# PIC18F57Q84_Curiosity_Nano_Target_MCU.net
KiCad netlist of a schematic drawn in Altium Designer
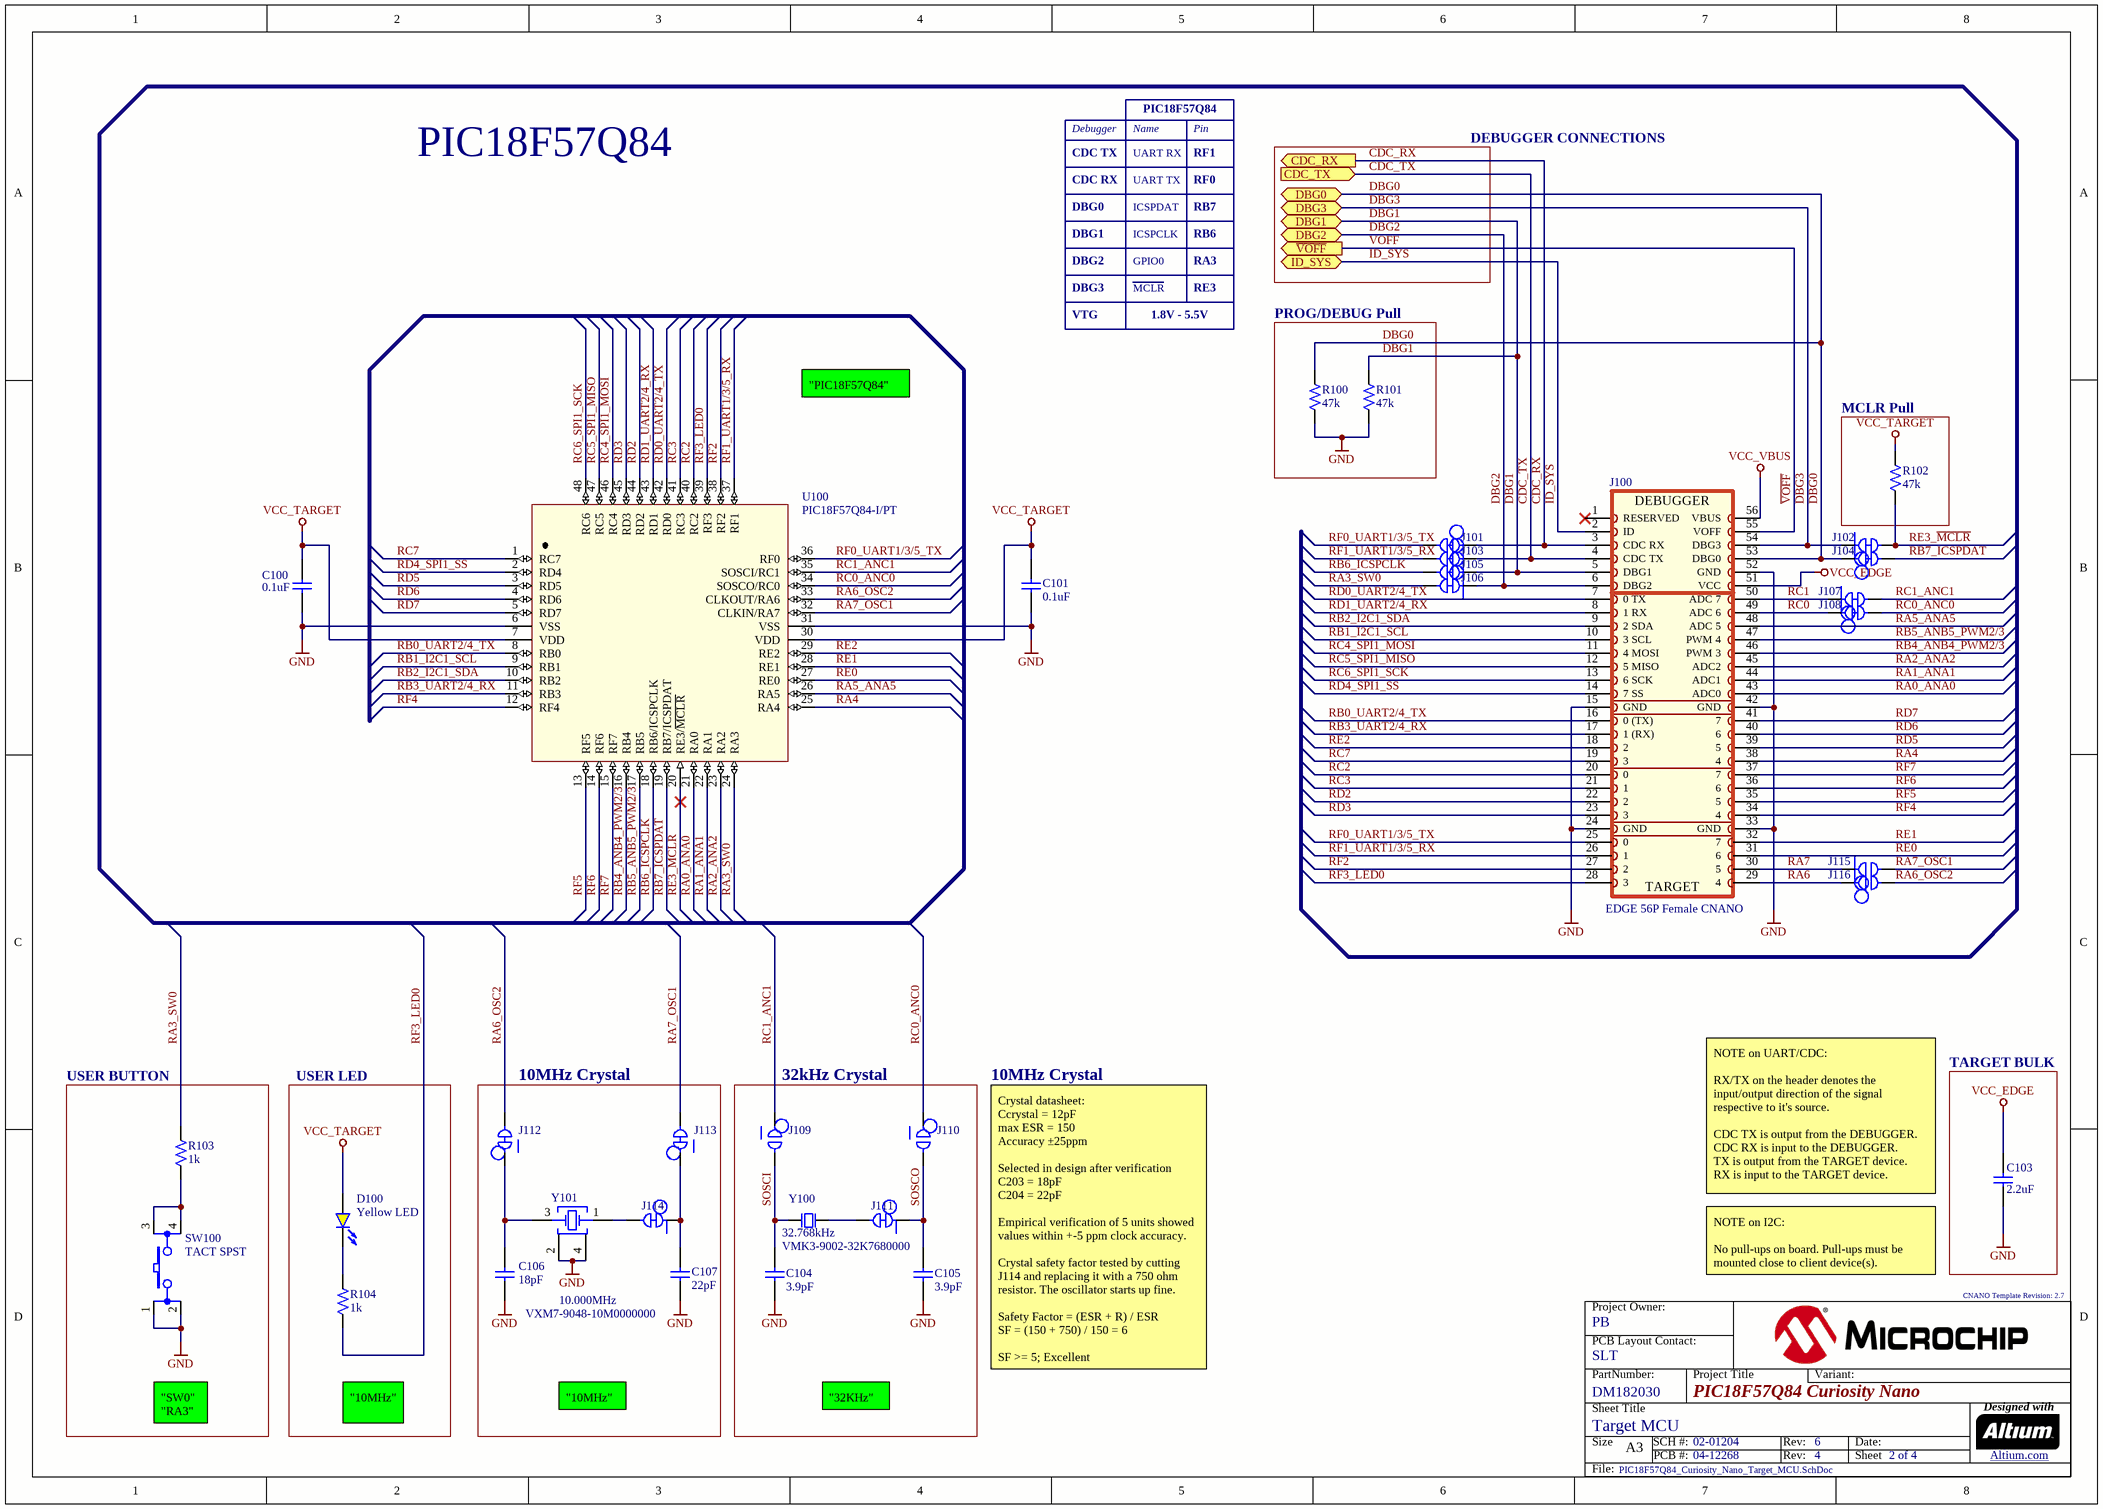
[diagram p0: PIC18F57Q84_Curiosity_Nano_Target_MCU.SchDoc]

(export (version "E")
  (design (tool "Eeschema 10.0.6"))
  (components
    (comp (ref "C100")
      (value "0.1uF")
      (footprint "CAP_C_0402")
      (fields
        (field (name "VOLTAGE") "16V")
        (field (name "TOLERANCE") "10%")
        (field (name "Comment") "Capacitor NP")
      )
      (libsource (lib "MCHP-CDB") (part "Capacitor NP"))
    )
    (comp (ref "C101")
      (value "0.1uF")
      (footprint "CAP_C_0402")
      (fields
        (field (name "VOLTAGE") "16V")
        (field (name "TOLERANCE") "10%")
        (field (name "Comment") "Capacitor NP")
      )
      (libsource (lib "MCHP-CDB") (part "Capacitor NP"))
    )
    (comp (ref "C103")
      (value "2.2uF")
      (footprint "CAP_C_0402")
      (fields
        (field (name "VOLTAGE") "10V")
        (field (name "TOLERANCE") "10%")
        (field (name "Comment") "Capacitor NP")
      )
      (libsource (lib "MCHP-CDB") (part "Capacitor NP"))
    )
    (comp (ref "C104")
      (value "3.9pF")
      (footprint "CAP_C_0402")
      (fields
        (field (name "VOLTAGE") "50V")
        (field (name "TOLERANCE") "0.25pF")
        (field (name "Comment") "Capacitor NP")
      )
      (libsource (lib "MCHP-CDB") (part "Capacitor NP"))
    )
    (comp (ref "C105")
      (value "3.9pF")
      (footprint "CAP_C_0402")
      (fields
        (field (name "VOLTAGE") "50V")
        (field (name "TOLERANCE") "0.25pF")
        (field (name "Comment") "Capacitor NP")
      )
      (libsource (lib "MCHP-CDB") (part "Capacitor NP"))
    )
    (comp (ref "C106")
      (value "18pF")
      (footprint "CAP_C_0402")
      (fields
        (field (name "VOLTAGE") "50V")
        (field (name "TOLERANCE") "5%")
        (field (name "Comment") "Capacitor NP")
      )
      (libsource (lib "MCHP-CDB") (part "Capacitor NP"))
    )
    (comp (ref "C107")
      (value "22pF")
      (footprint "CAP_C_0402")
      (fields
        (field (name "VOLTAGE") "50V")
        (field (name "TOLERANCE") "5%")
        (field (name "Comment") "Capacitor NP")
      )
      (libsource (lib "MCHP-CDB") (part "Capacitor NP"))
    )
    (comp (ref "D100")
      (value "Yellow LED")
      (footprint "LED_0603_Yellow")
      (description "LED")
      (fields (field (name "Comment") "LED_yellow"))
      (libsource (lib "MCHP-CDB") (part "LED_yellow"))
    )
    (comp (ref "J100")
      (value "EDGE 56P Female CNANO")
      (footprint "CON_EDGE_CNANO-56")
      (fields (field (name "Comment") "CON EDGE CNANO-56"))
      (libsource (lib "MCHP-CDB") (part "CON EDGE CNANO-56"))
    )
    (comp (ref "J101")
      (value "CON JMPR LINK CLOSED")
      (footprint "CON_JMPR_0402_PCB_TRACE_LINK_0.9mm_PAD_0.6mm_PTH")
      (libsource (lib "MCHP-CDB") (part "CON JMPR LINK CLOSED"))
    )
    (comp (ref "J102")
      (value "CON JMPR LINK CLOSED")
      (footprint "CON_JMPR_0402_PCB_TRACE_LINK_0.9mm_PAD_0.6mm_PTH")
      (libsource (lib "") (part "CON JMPR LINK CLOSED_1"))
    )
    (comp (ref "J103")
      (value "CON JMPR LINK CLOSED")
      (footprint "CON_JMPR_0402_PCB_TRACE_LINK_0.9mm_PAD_0.6mm_PTH")
      (libsource (lib "MCHP-CDB") (part "CON JMPR LINK CLOSED"))
    )
    (comp (ref "J104")
      (value "CON JMPR LINK CLOSED")
      (footprint "CON_JMPR_0402_PCB_TRACE_LINK_0.9mm_PAD_0.6mm_PTH")
      (libsource (lib "") (part "CON JMPR LINK CLOSED_1"))
    )
    (comp (ref "J105")
      (value "CON JMPR LINK CLOSED")
      (footprint "CON_JMPR_0402_PCB_TRACE_LINK_0.9mm_PAD_0.6mm_PTH")
      (libsource (lib "MCHP-CDB") (part "CON JMPR LINK CLOSED"))
    )
    (comp (ref "J106")
      (value "CON JMPR LINK CLOSED")
      (footprint "CON_JMPR_0402_PCB_TRACE_LINK_0.9mm_PAD_0.6mm_PTH")
      (libsource (lib "MCHP-CDB") (part "CON JMPR LINK CLOSED"))
    )
    (comp (ref "J107")
      (value "CON JMPR LINK CLOSED")
      (footprint "CON_JMPR_0402_PCB_TRACE_LINK_0.9mm_PAD_0.6mm_PTH")
      (libsource (lib "") (part "CON JMPR LINK CLOSED_1"))
    )
    (comp (ref "J108")
      (value "CON JMPR LINK CLOSED")
      (footprint "CON_JMPR_0402_PCB_TRACE_LINK_0.9mm_PAD_0.6mm_PTH")
      (libsource (lib "") (part "CON JMPR LINK CLOSED_1"))
    )
    (comp (ref "J109")
      (value "CON JMPR SOLDER-STRAP OPEN SMD")
      (footprint "CON_JMPR_1mmX1mm_ROUND_SOLDER-STRAP")
      (libsource (lib "MCHP-CDB") (part "CON JMPR SOLDER-STRAP OPEN SMD"))
    )
    (comp (ref "J110")
      (value "CON JMPR SOLDER-STRAP OPEN SMD")
      (footprint "CON_JMPR_1mmX1mm_ROUND_SOLDER-STRAP")
      (libsource (lib "MCHP-CDB") (part "CON JMPR SOLDER-STRAP OPEN SMD"))
    )
    (comp (ref "J111")
      (value "CON JMPR LINK CLOSED")
      (footprint "CON_JMPR_0402_PCB_TRACE_LINK")
      (libsource (lib "MCHP-CDB") (part "CON JMPR LINK CLOSED"))
    )
    (comp (ref "J112")
      (value "CON JMPR LINK CLOSED")
      (footprint "CON_JMPR_0402_PCB_TRACE_LINK_0.9mm_PAD_0.6mm_PTH")
      (libsource (lib "") (part "CON JMPR LINK CLOSED_2"))
    )
    (comp (ref "J113")
      (value "CON JMPR LINK CLOSED")
      (footprint "CON_JMPR_0402_PCB_TRACE_LINK_0.9mm_PAD_0.6mm_PTH")
      (libsource (lib "") (part "CON JMPR LINK CLOSED_2"))
    )
    (comp (ref "J114")
      (value "CON JMPR LINK CLOSED")
      (footprint "CON_JMPR_0402_PCB_TRACE_LINK")
      (libsource (lib "MCHP-CDB") (part "CON JMPR LINK CLOSED"))
    )
    (comp (ref "J115")
      (value "CON JMPR SOLDER-STRAP OPEN SMD")
      (footprint "CON_JMPR_1mmX1mm_ROUND_SOLDER-STRAP")
      (libsource (lib "MCHP-CDB") (part "CON JMPR SOLDER-STRAP OPEN SMD"))
    )
    (comp (ref "J116")
      (value "CON JMPR SOLDER-STRAP OPEN SMD")
      (footprint "CON_JMPR_1mmX1mm_ROUND_SOLDER-STRAP")
      (libsource (lib "MCHP-CDB") (part "CON JMPR SOLDER-STRAP OPEN SMD"))
    )
    (comp (ref "R100")
      (value "47k")
      (footprint "RES_C_0402")
      (description "Resistor")
      (fields (field (name "TOLERANCE") "1%") (field (name "VOLTAGE") "50V"))
      (libsource (lib "MCHP-CDB") (part "Resistor"))
    )
    (comp (ref "R101")
      (value "47k")
      (footprint "RES_C_0402")
      (description "Resistor")
      (fields (field (name "TOLERANCE") "1%") (field (name "VOLTAGE") "50V"))
      (libsource (lib "MCHP-CDB") (part "Resistor"))
    )
    (comp (ref "R102")
      (value "47k")
      (footprint "RES_C_0402")
      (description "Resistor")
      (fields (field (name "TOLERANCE") "1%") (field (name "VOLTAGE") "50V"))
      (libsource (lib "MCHP-CDB") (part "Resistor"))
    )
    (comp (ref "R103")
      (value "1k")
      (footprint "RES_C_0402")
      (description "Resistor")
      (fields (field (name "TOLERANCE") "1%") (field (name "VOLTAGE") "50V"))
      (libsource (lib "") (part "Resistor_1"))
    )
    (comp (ref "R104")
      (value "1k")
      (footprint "RES_C_0402")
      (description "Resistor")
      (fields (field (name "TOLERANCE") "1%") (field (name "VOLTAGE") "50V"))
      (libsource (lib "") (part "Resistor_1"))
    )
    (comp (ref "SW100")
      (value "TACT SPST")
      (footprint "SW_TACT_SMD_DW_TS604VM1-035CR-R")
      (description "Switch")
      (fields (field (name "VOLTAGE") "12V") (field (name "Comment") "Switch 4 Pin"))
      (libsource (lib "MCHP-CDB") (part "Switch 4 Pin"))
    )
    (comp (ref "U100")
      (value "PIC18F57Q84-I/PT")
      (footprint "TQFP-48_7x7")
      (fields (field (name "Comment") "PIC18F5xQ84 TQFP-48"))
      (libsource (lib "MCHP-CDB") (part "PIC18F5xQ84 TQFP-48"))
    )
    (comp (ref "Y100")
      (value "32.768kHz")
      (footprint "CRYSTAL_VMK3_L3.2W1.5H0.9")
      (description "Crystal")
      (fields
        (field (name "MANUFACTURER PART NUMBER 1") "VMK3-9002-32K7680000")
        (field (name "Comment") "Crystal 2 Pins")
      )
      (libsource (lib "MCHP-CDB") (part "Crystal 2 Pins"))
    )
    (comp (ref "Y101")
      (value "10.000MHz")
      (footprint "CRYSTAL_L3.2W2.5H0.8")
      (description "Crystal")
      (fields
        (field (name "MANUFACTURER PART NUMBER 1") "VXM7-9048-10M0000000")
        (field (name "Comment") "Crystal 4 pins 1-3")
      )
      (libsource (lib "MCHP-CDB") (part "Crystal 4 pins 1-3"))
    )
  )
  (nets
    (net (code "1") (name "/CDC_RX") (class "Default")
      (node (ref "J100") (pin "3") (pinfunction "CDC_RX_3") (pintype "passive"))
      (node (ref "J101") (pin "1") (pinfunction "1_1") (pintype "passive"))
    )
    (net (code "2") (name "/CDC_TX") (class "Default")
      (node (ref "J100") (pin "4") (pinfunction "CDC_TX_4") (pintype "passive"))
      (node (ref "J103") (pin "1") (pinfunction "1_1") (pintype "passive"))
    )
    (net (code "3") (name "/DBG0") (class "Default")
      (node (ref "J100") (pin "53") (pinfunction "DBG0_53") (pintype "passive"))
      (node (ref "J104") (pin "1") (pinfunction "1_1") (pintype "passive"))
      (node (ref "R100") (pin "1") (pinfunction "1_1") (pintype "passive"))
    )
    (net (code "4") (name "/DBG1") (class "Default")
      (node (ref "J100") (pin "5") (pinfunction "DBG1_5") (pintype "passive"))
      (node (ref "J105") (pin "1") (pinfunction "1_1") (pintype "passive"))
      (node (ref "R101") (pin "1") (pinfunction "1_1") (pintype "passive"))
    )
    (net (code "5") (name "/DBG2") (class "Default")
      (node (ref "J100") (pin "6") (pinfunction "DBG2_6") (pintype "passive"))
      (node (ref "J106") (pin "1") (pinfunction "1_1") (pintype "passive"))
    )
    (net (code "6") (name "/DBG3") (class "Default")
      (node (ref "J100") (pin "54") (pinfunction "DBG3_54") (pintype "passive"))
      (node (ref "J102") (pin "1") (pinfunction "1_1") (pintype "passive"))
    )
    (net (code "7") (name "/ID_SYS") (class "Default")
      (node (ref "J100") (pin "2") (pinfunction "ID_2") (pintype "passive"))
    )
    (net (code "8") (name "/RA0_ANA0") (class "Default")
      (node (ref "J100") (pin "43") (pinfunction "ADC0_43") (pintype "passive"))
      (node (ref "U100") (pin "21") (pinfunction "RA0_21") (pintype "bidirectional"))
    )
    (net (code "9") (name "/RA1_ANA1") (class "Default")
      (node (ref "J100") (pin "44") (pinfunction "ADC1_44") (pintype "passive"))
      (node (ref "U100") (pin "22") (pinfunction "RA1_22") (pintype "bidirectional"))
    )
    (net (code "10") (name "/RA2_ANA2") (class "Default")
      (node (ref "J100") (pin "45") (pinfunction "ADC2_45") (pintype "passive"))
      (node (ref "U100") (pin "23") (pinfunction "RA2_23") (pintype "bidirectional"))
    )
    (net (code "11") (name "/RA3_SW0") (class "Default")
      (node (ref "J106") (pin "2") (pinfunction "2_2") (pintype "passive"))
      (node (ref "R103") (pin "1") (pinfunction "1_1") (pintype "passive"))
      (node (ref "U100") (pin "24") (pinfunction "RA3_24") (pintype "bidirectional"))
    )
    (net (code "12") (name "/RA4") (class "Default")
      (node (ref "J100") (pin "38") (pinfunction "4_38") (pintype "passive"))
      (node (ref "U100") (pin "25") (pinfunction "RA4_25") (pintype "bidirectional"))
    )
    (net (code "13") (name "/RA5_ANA5") (class "Default")
      (node (ref "J100") (pin "48") (pinfunction "ADC_5_48") (pintype "passive"))
      (node (ref "U100") (pin "26") (pinfunction "RA5_26") (pintype "bidirectional"))
    )
    (net (code "14") (name "/RA6") (class "Default")
      (node (ref "J100") (pin "29") (pinfunction "4_29") (pintype "passive"))
      (node (ref "J116") (pin "1") (pinfunction "1_1") (pintype "passive"))
    )
    (net (code "15") (name "/RA6_OSC2") (class "Default")
      (node (ref "J112") (pin "2") (pinfunction "2_2") (pintype "passive"))
      (node (ref "J116") (pin "2") (pinfunction "2_2") (pintype "passive"))
      (node (ref "U100") (pin "33") (pinfunction "CLKOUT/RA6_33") (pintype "bidirectional"))
    )
    (net (code "16") (name "/RA7") (class "Default")
      (node (ref "J100") (pin "30") (pinfunction "5_30") (pintype "passive"))
      (node (ref "J115") (pin "1") (pinfunction "1_1") (pintype "passive"))
    )
    (net (code "17") (name "/RA7_OSC1") (class "Default")
      (node (ref "J113") (pin "2") (pinfunction "2_2") (pintype "passive"))
      (node (ref "J115") (pin "2") (pinfunction "2_2") (pintype "passive"))
      (node (ref "U100") (pin "32") (pinfunction "CLKIN/RA7_32") (pintype "bidirectional"))
    )
    (net (code "18") (name "/RB0_UART2{slash}4_TX") (class "Default")
      (node (ref "J100") (pin "16") (pinfunction "0_(TX)_16") (pintype "passive"))
      (node (ref "U100") (pin "8") (pinfunction "RB0_8") (pintype "bidirectional"))
    )
    (net (code "19") (name "/RB1_I2C1_SCL") (class "Default")
      (node (ref "J100") (pin "10") (pinfunction "3_SCL_10") (pintype "passive"))
      (node (ref "U100") (pin "9") (pinfunction "RB1_9") (pintype "bidirectional"))
    )
    (net (code "20") (name "/RB2_I2C1_SDA") (class "Default")
      (node (ref "J100") (pin "9") (pinfunction "2_SDA_9") (pintype "passive"))
      (node (ref "U100") (pin "10") (pinfunction "RB2_10") (pintype "bidirectional"))
    )
    (net (code "21") (name "/RB3_UART2{slash}4_RX") (class "Default")
      (node (ref "J100") (pin "17") (pinfunction "1_(RX)_17") (pintype "passive"))
      (node (ref "U100") (pin "11") (pinfunction "RB3_11") (pintype "bidirectional"))
    )
    (net (code "22") (name "/RB4_ANB4_PWM2{slash}3") (class "Default")
      (node (ref "J100") (pin "46") (pinfunction "PWM_3_46") (pintype "passive"))
      (node (ref "U100") (pin "16") (pinfunction "RB4_16") (pintype "bidirectional"))
    )
    (net (code "23") (name "/RB5_ANB5_PWM2{slash}3") (class "Default")
      (node (ref "J100") (pin "47") (pinfunction "PWM_4_47") (pintype "passive"))
      (node (ref "U100") (pin "17") (pinfunction "RB5_17") (pintype "bidirectional"))
    )
    (net (code "24") (name "/RB6_ICSPCLK") (class "Default")
      (node (ref "J105") (pin "2") (pinfunction "2_2") (pintype "passive"))
      (node (ref "U100") (pin "18") (pinfunction "RB6/ICSPCLK_18") (pintype "bidirectional"))
    )
    (net (code "25") (name "/RB7_ICSPDAT") (class "Default")
      (node (ref "J104") (pin "2") (pinfunction "2_2") (pintype "passive"))
      (node (ref "U100") (pin "19") (pinfunction "RB7/ICSPDAT_19") (pintype "bidirectional"))
    )
    (net (code "26") (name "/RC0") (class "Default")
      (node (ref "J100") (pin "49") (pinfunction "ADC_6_49") (pintype "passive"))
      (node (ref "J108") (pin "1") (pinfunction "1_1") (pintype "passive"))
    )
    (net (code "27") (name "/RC0_ANC0") (class "Default")
      (node (ref "J108") (pin "2") (pinfunction "2_2") (pintype "passive"))
      (node (ref "J110") (pin "1") (pinfunction "1_1") (pintype "passive"))
      (node (ref "U100") (pin "34") (pinfunction "SOSCO/RC0_34") (pintype "bidirectional"))
    )
    (net (code "28") (name "/RC1") (class "Default")
      (node (ref "J100") (pin "50") (pinfunction "ADC_7_50") (pintype "passive"))
      (node (ref "J107") (pin "1") (pinfunction "1_1") (pintype "passive"))
    )
    (net (code "29") (name "/RC1_ANC1") (class "Default")
      (node (ref "J107") (pin "2") (pinfunction "2_2") (pintype "passive"))
      (node (ref "J109") (pin "1") (pinfunction "1_1") (pintype "passive"))
      (node (ref "U100") (pin "35") (pinfunction "SOSCI/RC1_35") (pintype "bidirectional"))
    )
    (net (code "30") (name "/RC2") (class "Default")
      (node (ref "J100") (pin "20") (pinfunction "0_20") (pintype "passive"))
      (node (ref "U100") (pin "40") (pinfunction "RC2_40") (pintype "bidirectional"))
    )
    (net (code "31") (name "/RC3") (class "Default")
      (node (ref "J100") (pin "21") (pinfunction "1_21") (pintype "passive"))
      (node (ref "U100") (pin "41") (pinfunction "RC3_41") (pintype "bidirectional"))
    )
    (net (code "32") (name "/RC4_SPI1_MOSI") (class "Default")
      (node (ref "J100") (pin "11") (pinfunction "4_MOSI_11") (pintype "passive"))
      (node (ref "U100") (pin "46") (pinfunction "RC4_46") (pintype "bidirectional"))
    )
    (net (code "33") (name "/RC5_SPI1_MISO") (class "Default")
      (node (ref "J100") (pin "12") (pinfunction "5_MISO_12") (pintype "passive"))
      (node (ref "U100") (pin "47") (pinfunction "RC5_47") (pintype "bidirectional"))
    )
    (net (code "34") (name "/RC6_SPI1_SCK") (class "Default")
      (node (ref "J100") (pin "13") (pinfunction "6_SCK_13") (pintype "passive"))
      (node (ref "U100") (pin "48") (pinfunction "RC6_48") (pintype "bidirectional"))
    )
    (net (code "35") (name "/RC7") (class "Default")
      (node (ref "J100") (pin "19") (pinfunction "3_19") (pintype "passive"))
      (node (ref "U100") (pin "1") (pinfunction "RC7_1") (pintype "bidirectional"))
    )
    (net (code "36") (name "/RD0_UART2{slash}4_TX") (class "Default")
      (node (ref "J100") (pin "7") (pinfunction "0_TX_7") (pintype "passive"))
      (node (ref "U100") (pin "42") (pinfunction "RD0_42") (pintype "bidirectional"))
    )
    (net (code "37") (name "/RD1_UART2{slash}4_RX") (class "Default")
      (node (ref "J100") (pin "8") (pinfunction "1_RX_8") (pintype "passive"))
      (node (ref "U100") (pin "43") (pinfunction "RD1_43") (pintype "bidirectional"))
    )
    (net (code "38") (name "/RD2") (class "Default")
      (node (ref "J100") (pin "22") (pinfunction "2_22") (pintype "passive"))
      (node (ref "U100") (pin "44") (pinfunction "RD2_44") (pintype "bidirectional"))
    )
    (net (code "39") (name "/RD3") (class "Default")
      (node (ref "J100") (pin "23") (pinfunction "3_23") (pintype "passive"))
      (node (ref "U100") (pin "45") (pinfunction "RD3_45") (pintype "bidirectional"))
    )
    (net (code "40") (name "/RD4_SPI1_SS") (class "Default")
      (node (ref "J100") (pin "14") (pinfunction "7_SS_14") (pintype "passive"))
      (node (ref "U100") (pin "2") (pinfunction "RD4_2") (pintype "bidirectional"))
    )
    (net (code "41") (name "/RD5") (class "Default")
      (node (ref "J100") (pin "39") (pinfunction "5_39") (pintype "passive"))
      (node (ref "U100") (pin "3") (pinfunction "RD5_3") (pintype "bidirectional"))
    )
    (net (code "42") (name "/RD6") (class "Default")
      (node (ref "J100") (pin "40") (pinfunction "6_40") (pintype "passive"))
      (node (ref "U100") (pin "4") (pinfunction "RD6_4") (pintype "bidirectional"))
    )
    (net (code "43") (name "/RD7") (class "Default")
      (node (ref "J100") (pin "41") (pinfunction "7_41") (pintype "passive"))
      (node (ref "U100") (pin "5") (pinfunction "RD7_5") (pintype "bidirectional"))
    )
    (net (code "44") (name "/RE0") (class "Default")
      (node (ref "J100") (pin "31") (pinfunction "6_31") (pintype "passive"))
      (node (ref "U100") (pin "27") (pinfunction "RE0_27") (pintype "bidirectional"))
    )
    (net (code "45") (name "/RE1") (class "Default")
      (node (ref "J100") (pin "32") (pinfunction "7_32") (pintype "passive"))
      (node (ref "U100") (pin "28") (pinfunction "RE1_28") (pintype "bidirectional"))
    )
    (net (code "46") (name "/RE2") (class "Default")
      (node (ref "J100") (pin "18") (pinfunction "2_18") (pintype "passive"))
      (node (ref "U100") (pin "29") (pinfunction "RE2_29") (pintype "bidirectional"))
    )
    (net (code "47") (name "/RE3_~{MCLR}") (class "Default")
      (node (ref "J102") (pin "2") (pinfunction "2_2") (pintype "passive"))
      (node (ref "R102") (pin "1") (pinfunction "1_1") (pintype "passive"))
      (node (ref "U100") (pin "20") (pinfunction "RE3/~{MCLR}_20") (pintype "input"))
    )
    (net (code "48") (name "/RF0_UART1{slash}3{slash}5_TX") (class "Default")
      (node (ref "J100") (pin "25") (pinfunction "0_25") (pintype "passive"))
      (node (ref "J101") (pin "2") (pinfunction "2_2") (pintype "passive"))
      (node (ref "U100") (pin "36") (pinfunction "RF0_36") (pintype "bidirectional"))
    )
    (net (code "49") (name "/RF1_UART1{slash}3{slash}5_RX") (class "Default")
      (node (ref "J100") (pin "26") (pinfunction "1_26") (pintype "passive"))
      (node (ref "J103") (pin "2") (pinfunction "2_2") (pintype "passive"))
      (node (ref "U100") (pin "37") (pinfunction "RF1_37") (pintype "bidirectional"))
    )
    (net (code "50") (name "/RF2") (class "Default")
      (node (ref "J100") (pin "27") (pinfunction "2_27") (pintype "passive"))
      (node (ref "U100") (pin "38") (pinfunction "RF2_38") (pintype "bidirectional"))
    )
    (net (code "51") (name "/RF3_LED0") (class "Default")
      (node (ref "J100") (pin "28") (pinfunction "3_28") (pintype "passive"))
      (node (ref "R104") (pin "1") (pinfunction "1_1") (pintype "passive"))
      (node (ref "U100") (pin "39") (pinfunction "RF3_39") (pintype "bidirectional"))
    )
    (net (code "52") (name "/RF4") (class "Default")
      (node (ref "J100") (pin "34") (pinfunction "4_34") (pintype "passive"))
      (node (ref "U100") (pin "12") (pinfunction "RF4_12") (pintype "bidirectional"))
    )
    (net (code "53") (name "/RF5") (class "Default")
      (node (ref "J100") (pin "35") (pinfunction "5_35") (pintype "passive"))
      (node (ref "U100") (pin "13") (pinfunction "RF5_13") (pintype "bidirectional"))
    )
    (net (code "54") (name "/RF6") (class "Default")
      (node (ref "J100") (pin "36") (pinfunction "6_36") (pintype "passive"))
      (node (ref "U100") (pin "14") (pinfunction "RF6_14") (pintype "bidirectional"))
    )
    (net (code "55") (name "/RF7") (class "Default")
      (node (ref "J100") (pin "37") (pinfunction "7_37") (pintype "passive"))
      (node (ref "U100") (pin "15") (pinfunction "RF7_15") (pintype "bidirectional"))
    )
    (net (code "56") (name "/SOSCI") (class "Default")
      (node (ref "C104") (pin "2") (pinfunction "2_2") (pintype "passive"))
      (node (ref "J109") (pin "2") (pinfunction "2_2") (pintype "passive"))
      (node (ref "Y100") (pin "1") (pinfunction "Osc1_1") (pintype "passive"))
    )
    (net (code "57") (name "/SOSCO") (class "Default")
      (node (ref "C105") (pin "1") (pinfunction "1_1") (pintype "passive"))
      (node (ref "J110") (pin "2") (pinfunction "2_2") (pintype "passive"))
      (node (ref "J111") (pin "1") (pinfunction "1_1") (pintype "passive"))
    )
    (net (code "58") (name "/~{VOFF}") (class "Default")
      (node (ref "J100") (pin "55") (pinfunction "VOFF_55") (pintype "passive"))
    )
    (net (code "59") (name "GND") (class "Default")
      (node (ref "C100") (pin "2") (pinfunction "2_2") (pintype "passive"))
      (node (ref "C101") (pin "1") (pinfunction "1_1") (pintype "passive"))
      (node (ref "C103") (pin "1") (pinfunction "1_1") (pintype "passive"))
      (node (ref "C104") (pin "1") (pinfunction "1_1") (pintype "passive"))
      (node (ref "C105") (pin "2") (pinfunction "2_2") (pintype "passive"))
      (node (ref "C106") (pin "1") (pinfunction "1_1") (pintype "passive"))
      (node (ref "C107") (pin "1") (pinfunction "1_1") (pintype "passive"))
      (node (ref "J100") (pin "15") (pinfunction "GND_15") (pintype "power_in"))
      (node (ref "J100") (pin "24") (pinfunction "GND_24") (pintype "power_in"))
      (node (ref "J100") (pin "33") (pinfunction "GND_33") (pintype "power_in"))
      (node (ref "J100") (pin "42") (pinfunction "GND_42") (pintype "power_in"))
      (node (ref "J100") (pin "52") (pinfunction "GND_52") (pintype "power_in"))
      (node (ref "R100") (pin "2") (pinfunction "2_2") (pintype "passive"))
      (node (ref "R101") (pin "2") (pinfunction "2_2") (pintype "passive"))
      (node (ref "SW100") (pin "1") (pinfunction "1_1") (pintype "passive"))
      (node (ref "SW100") (pin "2") (pinfunction "2_2") (pintype "passive"))
      (node (ref "U100") (pin "31") (pinfunction "VSS_31") (pintype "power_in"))
      (node (ref "U100") (pin "6") (pinfunction "VSS_6") (pintype "power_in"))
      (node (ref "Y101") (pin "2") (pintype "passive"))
      (node (ref "Y101") (pin "4") (pintype "passive"))
    )
    (net (code "60") (name "Net-(C106-Pad2)") (class "Default")
      (node (ref "C106") (pin "2") (pinfunction "2_2") (pintype "passive"))
      (node (ref "J112") (pin "1") (pinfunction "1_1") (pintype "passive"))
      (node (ref "Y101") (pin "3") (pintype "passive"))
    )
    (net (code "61") (name "Net-(C107-Pad2)") (class "Default")
      (node (ref "C107") (pin "2") (pinfunction "2_2") (pintype "passive"))
      (node (ref "J113") (pin "1") (pinfunction "1_1") (pintype "passive"))
      (node (ref "J114") (pin "1") (pinfunction "1_1") (pintype "passive"))
    )
    (net (code "62") (name "Net-(D100-K)") (class "Default")
      (node (ref "D100") (pin "2") (pinfunction "K_2") (pintype "passive"))
      (node (ref "R104") (pin "2") (pinfunction "2_2") (pintype "passive"))
    )
    (net (code "63") (name "Net-(J114-Pad2)") (class "Default")
      (node (ref "J114") (pin "2") (pinfunction "2_2") (pintype "passive"))
      (node (ref "Y101") (pin "1") (pintype "passive"))
    )
    (net (code "64") (name "Net-(R103-Pad2)") (class "Default")
      (node (ref "R103") (pin "2") (pinfunction "2_2") (pintype "passive"))
      (node (ref "SW100") (pin "3") (pinfunction "3_3") (pintype "passive"))
      (node (ref "SW100") (pin "4") (pinfunction "4_4") (pintype "passive"))
    )
    (net (code "65") (name "Net-(Y100-Osc2)") (class "Default")
      (node (ref "J111") (pin "2") (pinfunction "2_2") (pintype "passive"))
      (node (ref "Y100") (pin "2") (pinfunction "Osc2_2") (pintype "passive"))
    )
    (net (code "66") (name "VCC_EDGE") (class "Default")
      (node (ref "C103") (pin "2") (pinfunction "2_2") (pintype "passive"))
      (node (ref "J100") (pin "51") (pinfunction "VCC_51") (pintype "power_in"))
    )
    (net (code "67") (name "VCC_TARGET") (class "Default")
      (node (ref "C100") (pin "1") (pinfunction "1_1") (pintype "passive"))
      (node (ref "C101") (pin "2") (pinfunction "2_2") (pintype "passive"))
      (node (ref "D100") (pin "1") (pinfunction "A_1") (pintype "passive"))
      (node (ref "R102") (pin "2") (pinfunction "2_2") (pintype "passive"))
      (node (ref "U100") (pin "30") (pinfunction "VDD_30") (pintype "power_in"))
      (node (ref "U100") (pin "7") (pinfunction "VDD_7") (pintype "power_in"))
    )
    (net (code "68") (name "VCC_VBUS") (class "Default")
      (node (ref "J100") (pin "56") (pinfunction "VBUS_56") (pintype "passive"))
    )
    (net (code "69") (name "unconnected-(J100-RESERVED-Pad1)") (class "Default")
      (node (ref "J100") (pin "1") (pinfunction "RESERVED_1") (pintype "passive+no_connect"))
    )
  )
)
